# untitled.net
KiCad netlist of a schematic drawn in EAGLE
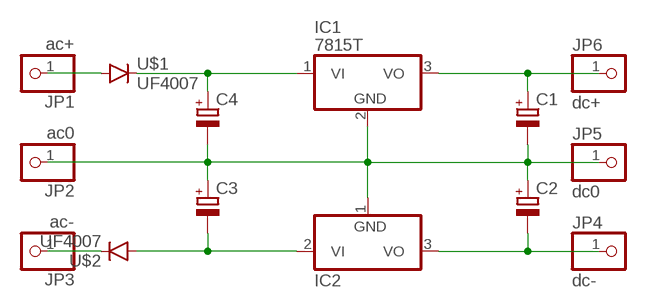
[diagram p0: schematic, sheet 1]

(export (version "E")
  (design (tool "Eeschema 10.0.6"))
  (components
    (comp (ref "C1")
      (value "CPOL-EUE5-10.5")
      (footprint "eagle-import:E5-10,5")
      (libsource (lib "eagle-import") (part "CPOL-EUE5-10.5"))
    )
    (comp (ref "C2")
      (value "CPOL-EUE5-10.5")
      (footprint "eagle-import:E5-10,5")
      (libsource (lib "eagle-import") (part "CPOL-EUE5-10.5"))
    )
    (comp (ref "C3")
      (value "CPOL-EUE5-10.5")
      (footprint "eagle-import:E5-10,5")
      (libsource (lib "eagle-import") (part "CPOL-EUE5-10.5"))
    )
    (comp (ref "C4")
      (value "CPOL-EUE5-10.5")
      (footprint "eagle-import:E5-10,5")
      (libsource (lib "eagle-import") (part "CPOL-EUE5-10.5"))
    )
    (comp (ref "IC1")
      (value "7815T")
      (footprint "eagle-import:TO220H")
      (libsource (lib "eagle-import") (part "78T15"))
    )
    (comp (ref "IC2")
      (value "7915T")
      (footprint "eagle-import:TO220H")
      (libsource (lib "eagle-import") (part "79T15"))
    )
    (comp (ref "JP1")
      (value "ac+")
      (footprint "eagle-import:1X01")
      (libsource (lib "eagle-import") (part "PINHD-1X1"))
    )
    (comp (ref "JP2")
      (value "ac0")
      (footprint "eagle-import:1X01")
      (libsource (lib "eagle-import") (part "PINHD-1X1"))
    )
    (comp (ref "JP3")
      (value "ac-")
      (footprint "eagle-import:1X01")
      (libsource (lib "eagle-import") (part "PINHD-1X1"))
    )
    (comp (ref "JP4")
      (value "dc-")
      (footprint "eagle-import:1X01")
      (libsource (lib "eagle-import") (part "PINHD-1X1"))
    )
    (comp (ref "JP5")
      (value "dc0")
      (footprint "eagle-import:1X01")
      (libsource (lib "eagle-import") (part "PINHD-1X1"))
    )
    (comp (ref "JP6")
      (value "dc+")
      (footprint "eagle-import:1X01")
      (libsource (lib "eagle-import") (part "PINHD-1X1"))
    )
    (comp (ref "U$1")
      (value "UF4007")
      (footprint "eagle-import:SMA-DIODE")
      (libsource (lib "eagle-import") (part "UF4007"))
    )
    (comp (ref "U$2")
      (value "UF4007")
      (footprint "eagle-import:SMA-DIODE")
      (libsource (lib "eagle-import") (part "UF4007"))
    )
  )
  (nets
    (net (code "1") (name "Net-(IC1-GND)") (class "Default")
      (node (ref "C1") (pin "-") (pinfunction "-_-") (pintype "passive"))
      (node (ref "C2") (pin "+") (pinfunction "+_+") (pintype "passive"))
      (node (ref "C3") (pin "+") (pinfunction "+_+") (pintype "passive"))
      (node (ref "C4") (pin "-") (pinfunction "-_-") (pintype "passive"))
      (node (ref "IC1") (pin "2") (pinfunction "GND_2") (pintype "passive"))
      (node (ref "IC2") (pin "1") (pinfunction "GND_1") (pintype "passive"))
      (node (ref "JP2") (pin "1") (pinfunction "1_1") (pintype "passive"))
      (node (ref "JP5") (pin "1") (pinfunction "1_1") (pintype "passive"))
    )
    (net (code "2") (name "Net-(IC1-VI)") (class "Default")
      (node (ref "C4") (pin "+") (pinfunction "+_+") (pintype "passive"))
      (node (ref "IC1") (pin "1") (pinfunction "VI_1") (pintype "input"))
      (node (ref "U$1") (pin "C") (pinfunction "C_C") (pintype "passive"))
    )
    (net (code "3") (name "Net-(IC1-VO)") (class "Default")
      (node (ref "C1") (pin "+") (pinfunction "+_+") (pintype "passive"))
      (node (ref "IC1") (pin "3") (pinfunction "VO_3") (pintype "passive"))
      (node (ref "JP6") (pin "1") (pinfunction "1_1") (pintype "passive"))
    )
    (net (code "4") (name "Net-(IC2-VI)") (class "Default")
      (node (ref "C3") (pin "-") (pinfunction "-_-") (pintype "passive"))
      (node (ref "IC2") (pin "2") (pinfunction "VI_2") (pintype "input"))
      (node (ref "U$2") (pin "A") (pinfunction "A_A") (pintype "passive"))
    )
    (net (code "5") (name "Net-(IC2-VO)") (class "Default")
      (node (ref "C2") (pin "-") (pinfunction "-_-") (pintype "passive"))
      (node (ref "IC2") (pin "3") (pinfunction "VO_3") (pintype "passive"))
      (node (ref "JP4") (pin "1") (pinfunction "1_1") (pintype "passive"))
    )
    (net (code "6") (name "Net-(JP1-Pad1)") (class "Default")
      (node (ref "JP1") (pin "1") (pinfunction "1_1") (pintype "passive"))
      (node (ref "U$1") (pin "A") (pinfunction "A_A") (pintype "passive"))
    )
    (net (code "7") (name "Net-(JP3-Pad1)") (class "Default")
      (node (ref "JP3") (pin "1") (pinfunction "1_1") (pintype "passive"))
      (node (ref "U$2") (pin "C") (pinfunction "C_C") (pintype "passive"))
    )
  )
)
